# resistor_board.net
KiCad netlist of a schematic drawn in EAGLE
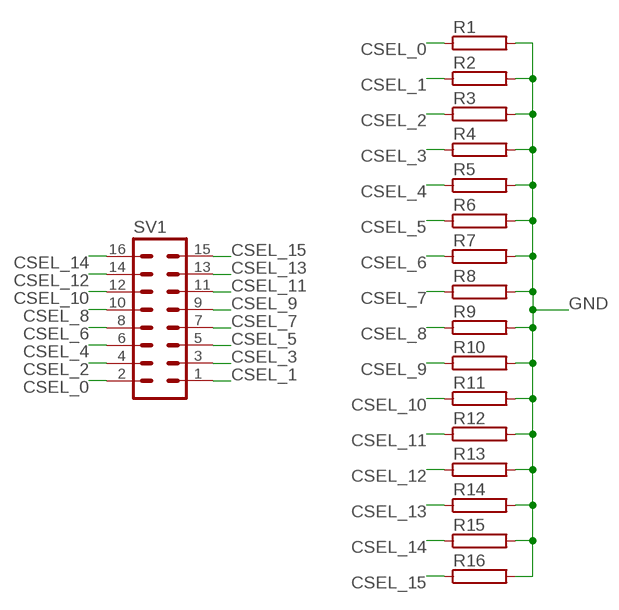
[diagram p0: schematic, sheet 1]

(export (version "E")
  (design (tool "Eeschema 10.0.6"))
  (components
    (comp (ref "R1")
      (value "RHPS58")
      (footprint "eagle-import:HPS58")
      (libsource (lib "eagle-import") (part "RHPS58"))
    )
    (comp (ref "R2")
      (value "RHPS58")
      (footprint "eagle-import:HPS58")
      (libsource (lib "eagle-import") (part "RHPS58"))
    )
    (comp (ref "R3")
      (value "RHPS58")
      (footprint "eagle-import:HPS58")
      (libsource (lib "eagle-import") (part "RHPS58"))
    )
    (comp (ref "R4")
      (value "RHPS58")
      (footprint "eagle-import:HPS58")
      (libsource (lib "eagle-import") (part "RHPS58"))
    )
    (comp (ref "R5")
      (value "RHPS58")
      (footprint "eagle-import:HPS58")
      (libsource (lib "eagle-import") (part "RHPS58"))
    )
    (comp (ref "R6")
      (value "RHPS58")
      (footprint "eagle-import:HPS58")
      (libsource (lib "eagle-import") (part "RHPS58"))
    )
    (comp (ref "R7")
      (value "RHPS58")
      (footprint "eagle-import:HPS58")
      (libsource (lib "eagle-import") (part "RHPS58"))
    )
    (comp (ref "R8")
      (value "RHPS58")
      (footprint "eagle-import:HPS58")
      (libsource (lib "eagle-import") (part "RHPS58"))
    )
    (comp (ref "R9")
      (value "RHPS58")
      (footprint "eagle-import:HPS58")
      (libsource (lib "eagle-import") (part "RHPS58"))
    )
    (comp (ref "R10")
      (value "RHPS58")
      (footprint "eagle-import:HPS58")
      (libsource (lib "eagle-import") (part "RHPS58"))
    )
    (comp (ref "R11")
      (value "RHPS58")
      (footprint "eagle-import:HPS58")
      (libsource (lib "eagle-import") (part "RHPS58"))
    )
    (comp (ref "R12")
      (value "RHPS58")
      (footprint "eagle-import:HPS58")
      (libsource (lib "eagle-import") (part "RHPS58"))
    )
    (comp (ref "R13")
      (value "RHPS58")
      (footprint "eagle-import:HPS58")
      (libsource (lib "eagle-import") (part "RHPS58"))
    )
    (comp (ref "R14")
      (value "RHPS58")
      (footprint "eagle-import:HPS58")
      (libsource (lib "eagle-import") (part "RHPS58"))
    )
    (comp (ref "R15")
      (value "RHPS58")
      (footprint "eagle-import:HPS58")
      (libsource (lib "eagle-import") (part "RHPS58"))
    )
    (comp (ref "R16")
      (value "RHPS58")
      (footprint "eagle-import:HPS58")
      (libsource (lib "eagle-import") (part "RHPS58"))
    )
    (comp (ref "SV1")
      (value "MA08-2")
      (footprint "eagle-import:MA08-2")
      (libsource (lib "eagle-import") (part "MA08-2"))
    )
  )
  (nets
    (net (code "1") (name "/CSEL_0") (class "Default")
      (node (ref "R1") (pin "1") (pinfunction "1_1") (pintype "passive"))
      (node (ref "SV1") (pin "2") (pinfunction "2_2") (pintype "passive"))
    )
    (net (code "2") (name "/CSEL_1") (class "Default")
      (node (ref "R2") (pin "1") (pinfunction "1_1") (pintype "passive"))
      (node (ref "SV1") (pin "1") (pinfunction "1_1") (pintype "passive"))
    )
    (net (code "3") (name "/CSEL_2") (class "Default")
      (node (ref "R3") (pin "1") (pinfunction "1_1") (pintype "passive"))
      (node (ref "SV1") (pin "4") (pinfunction "4_4") (pintype "passive"))
    )
    (net (code "4") (name "/CSEL_3") (class "Default")
      (node (ref "R4") (pin "1") (pinfunction "1_1") (pintype "passive"))
      (node (ref "SV1") (pin "3") (pinfunction "3_3") (pintype "passive"))
    )
    (net (code "5") (name "/CSEL_4") (class "Default")
      (node (ref "R5") (pin "1") (pinfunction "1_1") (pintype "passive"))
      (node (ref "SV1") (pin "6") (pinfunction "6_6") (pintype "passive"))
    )
    (net (code "6") (name "/CSEL_5") (class "Default")
      (node (ref "R6") (pin "1") (pinfunction "1_1") (pintype "passive"))
      (node (ref "SV1") (pin "5") (pinfunction "5_5") (pintype "passive"))
    )
    (net (code "7") (name "/CSEL_6") (class "Default")
      (node (ref "R7") (pin "1") (pinfunction "1_1") (pintype "passive"))
      (node (ref "SV1") (pin "8") (pinfunction "8_8") (pintype "passive"))
    )
    (net (code "8") (name "/CSEL_7") (class "Default")
      (node (ref "R8") (pin "1") (pinfunction "1_1") (pintype "passive"))
      (node (ref "SV1") (pin "7") (pinfunction "7_7") (pintype "passive"))
    )
    (net (code "9") (name "/CSEL_8") (class "Default")
      (node (ref "R9") (pin "1") (pinfunction "1_1") (pintype "passive"))
      (node (ref "SV1") (pin "10") (pinfunction "10_10") (pintype "passive"))
    )
    (net (code "10") (name "/CSEL_9") (class "Default")
      (node (ref "R10") (pin "1") (pinfunction "1_1") (pintype "passive"))
      (node (ref "SV1") (pin "9") (pinfunction "9_9") (pintype "passive"))
    )
    (net (code "11") (name "/CSEL_10") (class "Default")
      (node (ref "R11") (pin "1") (pinfunction "1_1") (pintype "passive"))
      (node (ref "SV1") (pin "12") (pinfunction "12_12") (pintype "passive"))
    )
    (net (code "12") (name "/CSEL_11") (class "Default")
      (node (ref "R12") (pin "1") (pinfunction "1_1") (pintype "passive"))
      (node (ref "SV1") (pin "11") (pinfunction "11_11") (pintype "passive"))
    )
    (net (code "13") (name "/CSEL_12") (class "Default")
      (node (ref "R13") (pin "1") (pinfunction "1_1") (pintype "passive"))
      (node (ref "SV1") (pin "14") (pinfunction "14_14") (pintype "passive"))
    )
    (net (code "14") (name "/CSEL_13") (class "Default")
      (node (ref "R14") (pin "1") (pinfunction "1_1") (pintype "passive"))
      (node (ref "SV1") (pin "13") (pinfunction "13_13") (pintype "passive"))
    )
    (net (code "15") (name "/CSEL_14") (class "Default")
      (node (ref "R15") (pin "1") (pinfunction "1_1") (pintype "passive"))
      (node (ref "SV1") (pin "16") (pinfunction "16_16") (pintype "passive"))
    )
    (net (code "16") (name "/CSEL_15") (class "Default")
      (node (ref "R16") (pin "1") (pinfunction "1_1") (pintype "passive"))
      (node (ref "SV1") (pin "15") (pinfunction "15_15") (pintype "passive"))
    )
    (net (code "17") (name "/GND") (class "Default")
      (node (ref "R1") (pin "2") (pinfunction "2_2") (pintype "passive"))
      (node (ref "R10") (pin "2") (pinfunction "2_2") (pintype "passive"))
      (node (ref "R11") (pin "2") (pinfunction "2_2") (pintype "passive"))
      (node (ref "R12") (pin "2") (pinfunction "2_2") (pintype "passive"))
      (node (ref "R13") (pin "2") (pinfunction "2_2") (pintype "passive"))
      (node (ref "R14") (pin "2") (pinfunction "2_2") (pintype "passive"))
      (node (ref "R15") (pin "2") (pinfunction "2_2") (pintype "passive"))
      (node (ref "R16") (pin "2") (pinfunction "2_2") (pintype "passive"))
      (node (ref "R2") (pin "2") (pinfunction "2_2") (pintype "passive"))
      (node (ref "R3") (pin "2") (pinfunction "2_2") (pintype "passive"))
      (node (ref "R4") (pin "2") (pinfunction "2_2") (pintype "passive"))
      (node (ref "R5") (pin "2") (pinfunction "2_2") (pintype "passive"))
      (node (ref "R6") (pin "2") (pinfunction "2_2") (pintype "passive"))
      (node (ref "R7") (pin "2") (pinfunction "2_2") (pintype "passive"))
      (node (ref "R8") (pin "2") (pinfunction "2_2") (pintype "passive"))
      (node (ref "R9") (pin "2") (pinfunction "2_2") (pintype "passive"))
    )
  )
)
